# Encoder.net
KiCad netlist of a schematic drawn in EAGLE
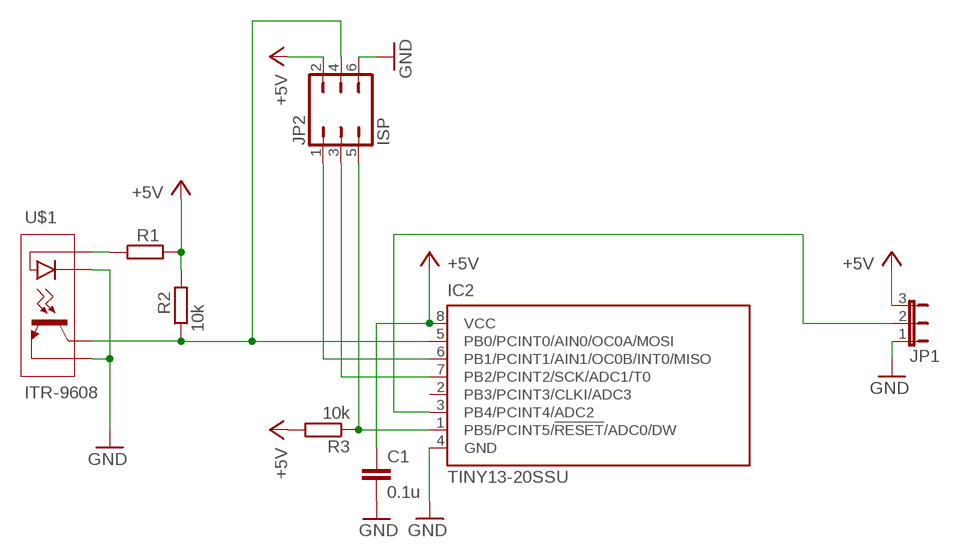
[diagram p0: schematic, sheet 1]

(export (version "E")
  (design (tool "Eeschema 10.0.6"))
  (components
    (comp (ref "C1")
      (value "0.1u")
      (footprint "eagle-import:C0805")
      (libsource (lib "eagle-import") (part "C-EUC0805"))
    )
    (comp (ref "IC2")
      (value "TINY13-20SSU")
      (footprint "eagle-import:8S1")
      (fields (field (name "MPN") "ATTINY13-20SSU"))
      (libsource (lib "eagle-import") (part "TINY13SSU-20"))
    )
    (comp (ref "JP1")
      (value "JP2E")
      (footprint "eagle-import:JP2")
      (libsource (lib "eagle-import") (part "JP2E"))
    )
    (comp (ref "JP2")
      (value "ISP")
      (footprint "eagle-import:JP3Q")
      (libsource (lib "eagle-import") (part "JP3Q"))
    )
    (comp (ref "R1")
      (value "R-EU_M0805")
      (footprint "eagle-import:M0805")
      (libsource (lib "eagle-import") (part "R-EU_M0805"))
    )
    (comp (ref "R2")
      (value "10k")
      (footprint "eagle-import:M0805")
      (libsource (lib "eagle-import") (part "R-EU_M0805"))
    )
    (comp (ref "R3")
      (value "10k")
      (footprint "eagle-import:M0805")
      (libsource (lib "eagle-import") (part "R-EU_M0805"))
    )
    (comp (ref "U$1")
      (value "ITR-9608")
      (footprint "eagle-import:ITR-9608-FOOTPRINT")
      (libsource (lib "eagle-import") (part "ITR-9608"))
    )
  )
  (nets
    (net (code "1") (name "+5V") (class "Default")
      (node (ref "C1") (pin "1") (pinfunction "1_1") (pintype "passive"))
      (node (ref "IC2") (pin "8") (pinfunction "VCC_8") (pintype "power_in"))
      (node (ref "JP1") (pin "3") (pinfunction "3_3") (pintype "passive"))
      (node (ref "JP2") (pin "2") (pinfunction "2_2") (pintype "passive"))
      (node (ref "R1") (pin "2") (pinfunction "2_2") (pintype "passive"))
      (node (ref "R2") (pin "2") (pinfunction "2_2") (pintype "passive"))
      (node (ref "R3") (pin "2") (pinfunction "2_2") (pintype "passive"))
    )
    (net (code "2") (name "GND") (class "Default")
      (node (ref "C1") (pin "2") (pinfunction "2_2") (pintype "passive"))
      (node (ref "IC2") (pin "4") (pinfunction "GND_4") (pintype "power_in"))
      (node (ref "JP1") (pin "1") (pinfunction "1_1") (pintype "passive"))
      (node (ref "JP2") (pin "6") (pinfunction "6_6") (pintype "passive"))
      (node (ref "U$1") (pin "E") (pinfunction "E_E") (pintype "bidirectional"))
      (node (ref "U$1") (pin "K") (pinfunction "K_K") (pintype "bidirectional"))
    )
    (net (code "3") (name "Net-(IC2-PB0{slash}PCINT0{slash}AIN0{slash}OC0A{slash}MOSI)") (class "Default")
      (node (ref "IC2") (pin "5") (pinfunction "PB0/PCINT0/AIN0/OC0A/MOSI_5") (pintype "bidirectional"))
      (node (ref "JP2") (pin "4") (pinfunction "4_4") (pintype "passive"))
      (node (ref "R2") (pin "1") (pinfunction "1_1") (pintype "passive"))
      (node (ref "U$1") (pin "C") (pinfunction "C_C") (pintype "bidirectional"))
    )
    (net (code "4") (name "Net-(IC2-PB1{slash}PCINT1{slash}AIN1{slash}OC0B{slash}INT0{slash}MISO)") (class "Default")
      (node (ref "IC2") (pin "6") (pinfunction "PB1/PCINT1/AIN1/OC0B/INT0/MISO_6") (pintype "bidirectional"))
      (node (ref "JP2") (pin "1") (pinfunction "1_1") (pintype "passive"))
    )
    (net (code "5") (name "Net-(IC2-PB2{slash}PCINT2{slash}SCK{slash}ADC1{slash}T0)") (class "Default")
      (node (ref "IC2") (pin "7") (pinfunction "PB2/PCINT2/SCK/ADC1/T0_7") (pintype "bidirectional"))
      (node (ref "JP2") (pin "3") (pinfunction "3_3") (pintype "passive"))
    )
    (net (code "6") (name "Net-(IC2-PB4{slash}PCINT4{slash}ADC2)") (class "Default")
      (node (ref "IC2") (pin "3") (pinfunction "PB4/PCINT4/ADC2_3") (pintype "bidirectional"))
      (node (ref "JP1") (pin "2") (pinfunction "2_2") (pintype "passive"))
    )
    (net (code "7") (name "Net-(IC2-PB5{slash}PCINT5{slash}~{RESET}{slash}ADC0{slash}DW)") (class "Default")
      (node (ref "IC2") (pin "1") (pinfunction "PB5/PCINT5/~{RESET}/ADC0/DW_1") (pintype "bidirectional"))
      (node (ref "JP2") (pin "5") (pinfunction "5_5") (pintype "passive"))
      (node (ref "R3") (pin "1") (pinfunction "1_1") (pintype "passive"))
    )
    (net (code "8") (name "Net-(R1-Pad1)") (class "Default")
      (node (ref "R1") (pin "1") (pinfunction "1_1") (pintype "passive"))
      (node (ref "U$1") (pin "A") (pinfunction "A_A") (pintype "bidirectional"))
    )
    (net (code "9") (name "unconnected-(IC2-PB3{slash}PCINT3{slash}CLKI{slash}ADC3-Pad2)") (class "Default")
      (node (ref "IC2") (pin "2") (pinfunction "PB3/PCINT3/CLKI/ADC3_2") (pintype "bidirectional"))
    )
  )
)
